# design.net
KiCad netlist of a schematic drawn in EasyEDA Pro
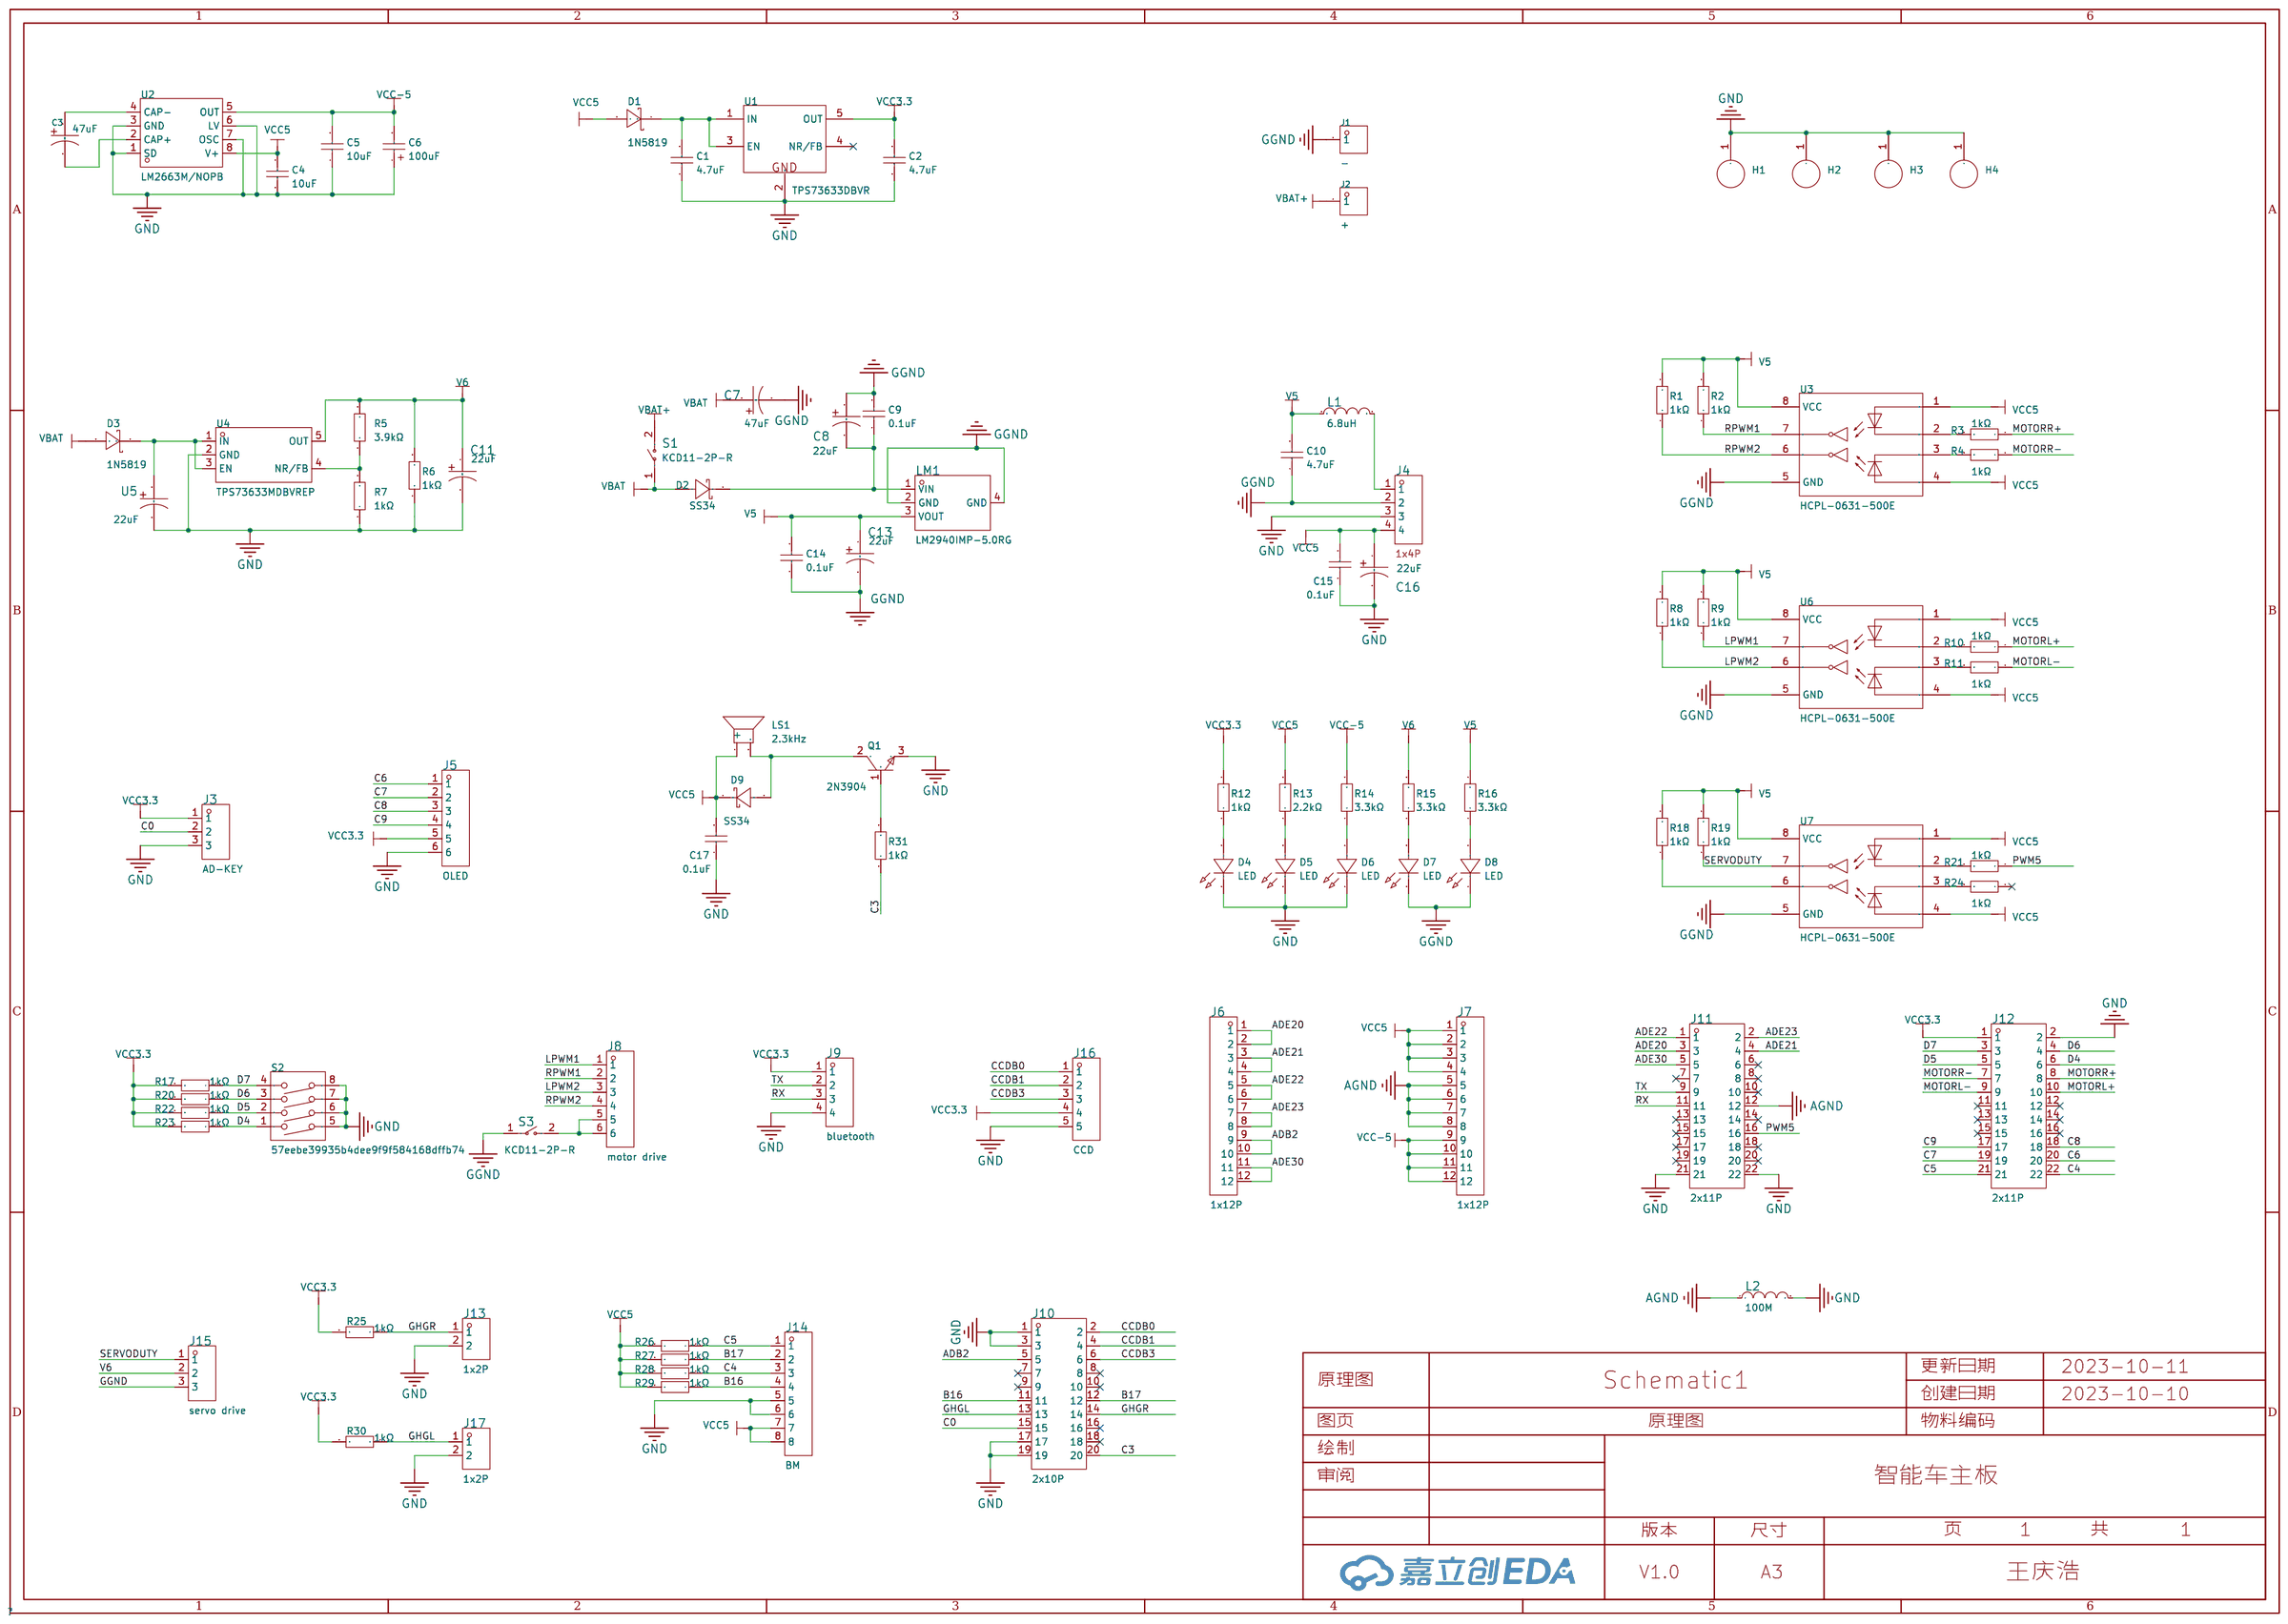
[diagram p0: schematic sheet]

(export (version "E")
  (design (tool "Eeschema 10.0.6"))
  (components
    (comp (ref "C1")
      (value "4.7uF")
      (footprint "easyedapro:C0805")
      (description "容值:10uF;精度:±10%;额定电压:25V;材质(温度系数):X5R;")
      (fields
        (field (name "Manufacturer Part") "CL21A106KAYNNNE")
        (field (name "Manufacturer") "SAMSUNG(三星)")
      )
      (libsource (lib "easyedapro") (part "CL21A106KAYNNNE"))
    )
    (comp (ref "C2")
      (value "4.7uF")
      (footprint "easyedapro:C0805")
      (description "容值:10uF;精度:±10%;额定电压:25V;材质(温度系数):X5R;")
      (fields
        (field (name "Manufacturer Part") "CL21A106KAYNNNE")
        (field (name "Manufacturer") "SAMSUNG(三星)")
      )
      (libsource (lib "easyedapro") (part "CL21A106KAYNNNE"))
    )
    (comp (ref "C3")
      (value "47uF")
      (footprint "easyedapro:CAP-SMD_L6.0-W3.2-R-RD")
      (description "容值:47uF;精度:±20%;额定电压:16V;等效串联电阻:1Ω;")
      (fields
        (field (name "Manufacturer Part") "293D476X0016C2TE3")
        (field (name "Manufacturer") "VISHAY(威世)")
      )
      (libsource (lib "easyedapro") (part "293D476X0016C2TE3"))
    )
    (comp (ref "C4")
      (value "10uF")
      (footprint "easyedapro:C0805")
      (description "容值:10uF;精度:±10%;额定电压:25V;材质(温度系数):X5R;")
      (fields
        (field (name "Manufacturer Part") "CL21A106KAYNNNE")
        (field (name "Manufacturer") "SAMSUNG(三星)")
      )
      (libsource (lib "easyedapro") (part "CL21A106KAYNNNE"))
    )
    (comp (ref "C5")
      (value "10uF")
      (footprint "easyedapro:C0805")
      (description "容值:10uF;精度:±10%;额定电压:25V;材质(温度系数):X5R;")
      (fields
        (field (name "Manufacturer Part") "CL21A106KAYNNNE")
        (field (name "Manufacturer") "SAMSUNG(三星)")
      )
      (libsource (lib "easyedapro") (part "CL21A106KAYNNNE"))
    )
    (comp (ref "C6")
      (value "100uF")
      (footprint "easyedapro:CAP-SMD_L3.2-W1.6-RD-C7171")
      (description "容值:10uF;精度:±10%;额定电压:16V;等效串联电阻:3Ω@100kHz;")
      (fields (field (name "Manufacturer Part") "TAJA106K016RNJ") (field (name "Manufacturer") "Kyocera AVX"))
      (libsource (lib "easyedapro") (part "TAJA106K016RNJ"))
    )
    (comp (ref "C7")
      (value "47uF")
      (footprint "easyedapro:CAP-SMD_L7.3-W4.3-RD")
      (fields
        (field (name "Manufacturer Part") "293D475X9035D2TE3")
        (field (name "Manufacturer") "VISHAY(威世)")
      )
      (libsource (lib "easyedapro") (part "293D475X9035D2TE3"))
    )
    (comp (ref "C8")
      (value "22uF")
      (footprint "easyedapro:CAP-SMD_L6.0-W3.2-R-RD")
      (description "容值:47uF;精度:±20%;额定电压:16V;等效串联电阻:1Ω;")
      (fields
        (field (name "Manufacturer Part") "293D476X0016C2TE3")
        (field (name "Manufacturer") "VISHAY(威世)")
      )
      (libsource (lib "easyedapro") (part "293D476X0016C2TE3"))
    )
    (comp (ref "C9")
      (value "0.1uF")
      (footprint "easyedapro:C0805")
      (description "容值:100nF;精度:±10%;额定电压:50V;材质(温度系数):X7R;")
      (fields
        (field (name "Manufacturer Part") "CC0805KRX7R9BB104")
        (field (name "Manufacturer") "YAGEO(国巨)")
      )
      (libsource (lib "easyedapro") (part "CC0805KRX7R9BB104"))
    )
    (comp (ref "C10")
      (value "4.7uF")
      (footprint "easyedapro:C0805")
      (description "容值:100nF;精度:±10%;额定电压:50V;材质(温度系数):X7R;")
      (fields
        (field (name "Manufacturer Part") "CC0805KRX7R9BB104")
        (field (name "Manufacturer") "YAGEO(国巨)")
      )
      (libsource (lib "easyedapro") (part "CC0805KRX7R9BB104"))
    )
    (comp (ref "C11")
      (value "22uF")
      (footprint "easyedapro:CAP-SMD_L7.3-W4.3-RD")
      (fields
        (field (name "Manufacturer Part") "293D475X9035D2TE3")
        (field (name "Manufacturer") "VISHAY(威世)")
      )
      (libsource (lib "easyedapro") (part "293D475X9035D2TE3"))
    )
    (comp (ref "C13")
      (value "22uF")
      (footprint "easyedapro:CAP-SMD_L7.3-W4.3-RD")
      (fields
        (field (name "Manufacturer Part") "293D475X9035D2TE3")
        (field (name "Manufacturer") "VISHAY(威世)")
      )
      (libsource (lib "easyedapro") (part "293D475X9035D2TE3"))
    )
    (comp (ref "C14")
      (value "0.1uF")
      (footprint "easyedapro:C0805")
      (description "容值:100nF;精度:±10%;额定电压:50V;材质(温度系数):X7R;")
      (fields
        (field (name "Manufacturer Part") "CC0805KRX7R9BB104")
        (field (name "Manufacturer") "YAGEO(国巨)")
      )
      (libsource (lib "easyedapro") (part "CC0805KRX7R9BB104"))
    )
    (comp (ref "C15")
      (value "0.1uF")
      (footprint "easyedapro:C0805")
      (description "容值:100nF;精度:±10%;额定电压:50V;材质(温度系数):X7R;")
      (fields
        (field (name "Manufacturer Part") "CC0805KRX7R9BB104")
        (field (name "Manufacturer") "YAGEO(国巨)")
      )
      (libsource (lib "easyedapro") (part "CC0805KRX7R9BB104"))
    )
    (comp (ref "C16")
      (value "22uF")
      (footprint "easyedapro:CAP-SMD_L7.3-W4.3-RD")
      (fields
        (field (name "Manufacturer Part") "293D475X9035D2TE3")
        (field (name "Manufacturer") "VISHAY(威世)")
      )
      (libsource (lib "easyedapro") (part "293D475X9035D2TE3"))
    )
    (comp (ref "C17")
      (value "0.1uF")
      (footprint "easyedapro:C0805")
      (description "容值:100nF;精度:±10%;额定电压:50V;材质(温度系数):X7R;")
      (fields
        (field (name "Manufacturer Part") "CC0805KRX7R9BB104")
        (field (name "Manufacturer") "YAGEO(国巨)")
      )
      (libsource (lib "easyedapro") (part "CC0805KRX7R9BB104"))
    )
    (comp (ref "D1")
      (value "1N5819")
      (footprint "easyedapro:SMA_L4.4-W2.6-LS5.0-RD")
      (description "直流反向耐压(Vr):40V;平均整流电流(Io):1A;正向压降(Vf):500mV@1A;")
      (fields (field (name "Manufacturer") "KEXIN(科信)"))
      (libsource (lib "easyedapro") (part "1N5819_C437199"))
    )
    (comp (ref "D2")
      (value "SS34")
      (footprint "easyedapro:SMA_L4.3-W2.5-LS5.0-RD")
      (description "二极管配置:独立式;直流反向耐压(Vr):40V;平均整流电流(Io):3A;正向压降(Vf):550mV@3A;")
      (fields (field (name "Manufacturer") "TWGMC(台湾迪嘉)"))
      (libsource (lib "easyedapro") (part "SS34_C727060"))
    )
    (comp (ref "D3")
      (value "1N5819")
      (footprint "easyedapro:SMA_L4.4-W2.6-LS5.0-RD")
      (description "直流反向耐压(Vr):40V;平均整流电流(Io):1A;正向压降(Vf):500mV@1A;")
      (fields (field (name "Manufacturer") "KEXIN(科信)"))
      (libsource (lib "easyedapro") (part "1N5819_C437199"))
    )
    (comp (ref "D4")
      (value "LED")
      (footprint "easyedapro:LED0805-RD_RED")
      (description "发光颜色:红灯;主波长:617nm~621nm;色温:-;功率:55mW;安装方式:正贴;")
      (fields (field (name "Manufacturer Part") "XL-2012SURC") (field (name "Manufacturer") "XINGLIGHT(成兴光)"))
      (libsource (lib "easyedapro") (part "XL-2012SURC"))
    )
    (comp (ref "D5")
      (value "LED")
      (footprint "easyedapro:LED0805-RD_RED")
      (description "发光颜色:红灯;主波长:617nm~621nm;色温:-;功率:55mW;安装方式:正贴;")
      (fields (field (name "Manufacturer Part") "XL-2012SURC") (field (name "Manufacturer") "XINGLIGHT(成兴光)"))
      (libsource (lib "easyedapro") (part "XL-2012SURC"))
    )
    (comp (ref "D6")
      (value "LED")
      (footprint "easyedapro:LED0805-RD_RED")
      (description "发光颜色:红灯;主波长:617nm~621nm;色温:-;功率:55mW;安装方式:正贴;")
      (fields (field (name "Manufacturer Part") "XL-2012SURC") (field (name "Manufacturer") "XINGLIGHT(成兴光)"))
      (libsource (lib "easyedapro") (part "XL-2012SURC"))
    )
    (comp (ref "D7")
      (value "LED")
      (footprint "easyedapro:LED0805-RD_RED")
      (description "发光颜色:红灯;主波长:617nm~621nm;色温:-;功率:55mW;安装方式:正贴;")
      (fields (field (name "Manufacturer Part") "XL-2012SURC") (field (name "Manufacturer") "XINGLIGHT(成兴光)"))
      (libsource (lib "easyedapro") (part "XL-2012SURC"))
    )
    (comp (ref "D8")
      (value "LED")
      (footprint "easyedapro:LED0805-RD_RED")
      (description "发光颜色:红灯;主波长:617nm~621nm;色温:-;功率:55mW;安装方式:正贴;")
      (fields (field (name "Manufacturer Part") "XL-2012SURC") (field (name "Manufacturer") "XINGLIGHT(成兴光)"))
      (libsource (lib "easyedapro") (part "XL-2012SURC"))
    )
    (comp (ref "D9")
      (value "SS34")
      (footprint "easyedapro:SMA_L4.3-W2.5-LS5.0-RD")
      (description "二极管配置:独立式;直流反向耐压(Vr):40V;平均整流电流(Io):3A;正向压降(Vf):550mV@3A;")
      (fields (field (name "Manufacturer") "TWGMC(台湾迪嘉)"))
      (libsource (lib "easyedapro") (part "SS34_C727060"))
    )
    (comp (ref "H1")
      (value "~")
      (footprint "easyedapro:固定孔封装")
      (description "铜柱孔")
      (libsource (lib "easyedapro") (part "固定孔"))
    )
    (comp (ref "H2")
      (value "~")
      (footprint "easyedapro:固定孔封装")
      (description "铜柱孔")
      (libsource (lib "easyedapro") (part "固定孔"))
    )
    (comp (ref "H3")
      (value "~")
      (footprint "easyedapro:固定孔封装")
      (description "铜柱孔")
      (libsource (lib "easyedapro") (part "固定孔"))
    )
    (comp (ref "H4")
      (value "~")
      (footprint "easyedapro:固定孔封装")
      (description "铜柱孔")
      (libsource (lib "easyedapro") (part "固定孔"))
    )
    (comp (ref "J1")
      (value "-")
      (footprint "easyedapro:HDR-SMD_1P-P2.54-V-M_XKB_R1")
      (fields (field (name "Manufacturer") "XKB Connectivity(中国星坤)"))
      (libsource (lib "easyedapro") (part "X6511WVS-01H-C60D48R1"))
    )
    (comp (ref "J2")
      (value "+")
      (footprint "easyedapro:HDR-SMD_1P-P2.54-V-M_XKB_R1")
      (fields (field (name "Manufacturer") "XKB Connectivity(中国星坤)"))
      (libsource (lib "easyedapro") (part "X6511WVS-01H-C60D48R1"))
    )
    (comp (ref "J3")
      (value "AD-KEY")
      (footprint "easyedapro:HDR-TH_3P-P2.54-V-M")
      (fields (field (name "Manufacturer Part") "PZ254V-11-03P") (field (name "Manufacturer") "XFCN(兴飞)"))
      (libsource (lib "easyedapro") (part "PZ254V-11-03P_C2937625"))
    )
    (comp (ref "J4")
      (value "bf6de8a097bd4b3495073099155543ed")
      (footprint "easyedapro:HDR-TH_4P-P2.54-V-M")
      (fields
        (field (name "Manufacturer Part") "PZ254V-11-04P")
        (field (name "Manufacturer") "XFCN(兴飞)")
        (field (name "Pin Structure") "1x4P")
      )
      (libsource (lib "easyedapro") (part "PZ254V-11-04P_C2691448"))
    )
    (comp (ref "J5")
      (value "OLED")
      (footprint "easyedapro:HDR-TH_6P-P2.54-V-M")
      (fields (field (name "Manufacturer Part") "PZ254V-11-06P") (field (name "Manufacturer") "XFCN(兴飞)"))
      (libsource (lib "easyedapro") (part "PZ254V-11-06P"))
    )
    (comp (ref "J6")
      (value "1x12P")
      (footprint "easyedapro:HDR-TH_12P-P2.54-V-M")
      (fields (field (name "Manufacturer Part") "PZ254V-11-12P") (field (name "Manufacturer") "XFCN(兴飞)"))
      (libsource (lib "easyedapro") (part "PZ254V-11-12P"))
    )
    (comp (ref "J7")
      (value "1x12P")
      (footprint "easyedapro:HDR-TH_12P-P2.54-V-M")
      (fields (field (name "Manufacturer Part") "PZ254V-11-12P") (field (name "Manufacturer") "XFCN(兴飞)"))
      (libsource (lib "easyedapro") (part "PZ254V-11-12P"))
    )
    (comp (ref "J8")
      (value "motor drive")
      (footprint "easyedapro:HDR-TH_6P-P2.54-V-M")
      (fields (field (name "Manufacturer Part") "PZ254V-11-06P") (field (name "Manufacturer") "XFCN(兴飞)"))
      (libsource (lib "easyedapro") (part "PZ254V-11-06P"))
    )
    (comp (ref "J9")
      (value "bluetooth")
      (footprint "easyedapro:HDR-TH_4P-P2.54-V-M")
      (fields (field (name "Manufacturer Part") "PZ254V-11-04P") (field (name "Manufacturer") "XFCN(兴飞)"))
      (libsource (lib "easyedapro") (part "PZ254V-11-04P_C2691448"))
    )
    (comp (ref "J10")
      (value "2x10P")
      (footprint "easyedapro:HDR-TH_20P-P2.54-V-M-R2-C10-S2.54")
      (fields (field (name "Manufacturer Part") "PZ254V-12-20P") (field (name "Manufacturer") "XFCN(兴飞)"))
      (libsource (lib "easyedapro") (part "PZ254V-12-20P"))
    )
    (comp (ref "J11")
      (value "2x11P")
      (footprint "easyedapro:HDR-TH_22P-P2.54-V-M-R2-C11-S2.54")
      (fields
        (field (name "Manufacturer Part") "PZ254-2-11-Z-8.5")
        (field (name "Manufacturer") "HCTL(华灿天禄)")
      )
      (libsource (lib "easyedapro") (part "PZ254-2-11-Z-8.5"))
    )
    (comp (ref "J12")
      (value "2x11P")
      (footprint "easyedapro:HDR-TH_22P-P2.54-V-M-R2-C11-S2.54")
      (fields
        (field (name "Manufacturer Part") "PZ254-2-11-Z-8.5")
        (field (name "Manufacturer") "HCTL(华灿天禄)")
      )
      (libsource (lib "easyedapro") (part "PZ254-2-11-Z-8.5"))
    )
    (comp (ref "J13")
      (value "1x2P")
      (footprint "easyedapro:HDR-TH_2P-P2.54-V-M")
      (fields (field (name "Manufacturer Part") "PZ254V-11-02P") (field (name "Manufacturer") "XFCN(兴飞)"))
      (libsource (lib "easyedapro") (part "PZ254V-11-02P"))
    )
    (comp (ref "J14")
      (value "BM")
      (footprint "easyedapro:HDR-TH_8P-P2.54-V-M")
      (fields (field (name "Manufacturer Part") "PZ254V-11-08P") (field (name "Manufacturer") "XFCN(兴飞)"))
      (libsource (lib "easyedapro") (part "PZ254V-11-08P"))
    )
    (comp (ref "J15")
      (value "servo drive")
      (footprint "easyedapro:HDR-TH_3P-P2.54-V-M")
      (fields (field (name "Manufacturer Part") "PZ254V-11-03P") (field (name "Manufacturer") "XFCN(兴飞)"))
      (libsource (lib "easyedapro") (part "PZ254V-11-03P_C2937625"))
    )
    (comp (ref "J16")
      (value "CCD")
      (footprint "easyedapro:HDR-TH_5P-P2.00-V-M")
      (fields (field (name "Manufacturer Part") "PZ200V-11-05P") (field (name "Manufacturer") "XFCN(兴飞)"))
      (libsource (lib "easyedapro") (part "PZ200V-11-05P"))
    )
    (comp (ref "J17")
      (value "1x2P")
      (footprint "easyedapro:HDR-TH_2P-P2.54-V-M")
      (fields (field (name "Manufacturer Part") "PZ254V-11-02P") (field (name "Manufacturer") "XFCN(兴飞)"))
      (libsource (lib "easyedapro") (part "PZ254V-11-02P"))
    )
    (comp (ref "L1")
      (value "6.8uH")
      (footprint "easyedapro:L0603")
      (description "电感值:10uH;精度:±10%;额定电流:3mA;饱和电流(Isat):-;直流电阻(DCR):1.85Ω;")
      (fields
        (field (name "Manufacturer Part") "SDFL1608S100KTF")
        (field (name "Manufacturer") "Sunlord(顺络)")
      )
      (libsource (lib "easyedapro") (part "SDFL1608S100KTF"))
    )
    (comp (ref "L2")
      (value "100M")
      (footprint "easyedapro:L0603")
      (description "电感值:10uH;精度:±10%;额定电流:3mA;饱和电流(Isat):-;直流电阻(DCR):1.85Ω;")
      (fields
        (field (name "Manufacturer Part") "SDFL1608S100KTF")
        (field (name "Manufacturer") "Sunlord(顺络)")
      )
      (libsource (lib "easyedapro") (part "SDFL1608S100KTF"))
    )
    (comp (ref "LM1")
      (value "LM2940IMP-5.0RG")
      (footprint "easyedapro:SOT-223-4_L6.5-W3.5-P2.30-LS7.0-BR")
      (fields (field (name "Manufacturer") "HGC(深圳汉芯)"))
      (libsource (lib "easyedapro") (part "LM2940IMP-5.0RG"))
    )
    (comp (ref "LS1")
      (value "2.3kHz")
      (footprint "easyedapro:BUZ-TH_BD12.0-P7.60-D0.6-FD")
      (description "驱动方式:有源(内含驱动线路);构造类型:电磁式;额定电压:5V;频率:2.3kHz;声压(SPL):85dB@5V,10cm;")
      (fields (field (name "Manufacturer Part") "TMB12A05") (field (name "Manufacturer") "华能"))
      (libsource (lib "easyedapro") (part "TMB12A05"))
    )
    (comp (ref "Q1")
      (value "2N3904")
      (footprint "easyedapro:TO-92-3_L4.6-W3.6-P1.30-L_2N3904")
      (fields (field (name "Manufacturer") "JSMSEMI(杰盛微)"))
      (libsource (lib "easyedapro") (part "2N3904_C2874602"))
    )
    (comp (ref "R1")
      (value "1kΩ")
      (footprint "easyedapro:R0805")
      (description "电阻类型:厚膜电阻;阻值:3.9kΩ;精度:±1%;功率:125mW;")
      (fields
        (field (name "Manufacturer Part") "0805W8F3901T5E")
        (field (name "Manufacturer") "UNI-ROYAL(厚声)")
      )
      (libsource (lib "easyedapro") (part "0805W8F3901T5E"))
    )
    (comp (ref "R2")
      (value "1kΩ")
      (footprint "easyedapro:R0805")
      (description "电阻类型:厚膜电阻;阻值:3.9kΩ;精度:±1%;功率:125mW;")
      (fields
        (field (name "Manufacturer Part") "0805W8F3901T5E")
        (field (name "Manufacturer") "UNI-ROYAL(厚声)")
      )
      (libsource (lib "easyedapro") (part "0805W8F3901T5E"))
    )
    (comp (ref "R3")
      (value "1kΩ")
      (footprint "easyedapro:R0805")
      (description "电阻类型:厚膜电阻;阻值:3.9kΩ;精度:±1%;功率:125mW;")
      (fields
        (field (name "Manufacturer Part") "0805W8F3901T5E")
        (field (name "Manufacturer") "UNI-ROYAL(厚声)")
      )
      (libsource (lib "easyedapro") (part "0805W8F3901T5E"))
    )
    (comp (ref "R4")
      (value "1kΩ")
      (footprint "easyedapro:R0805")
      (description "电阻类型:厚膜电阻;阻值:3.9kΩ;精度:±1%;功率:125mW;")
      (fields
        (field (name "Manufacturer Part") "0805W8F3901T5E")
        (field (name "Manufacturer") "UNI-ROYAL(厚声)")
      )
      (libsource (lib "easyedapro") (part "0805W8F3901T5E"))
    )
    (comp (ref "R5")
      (value "3.9kΩ")
      (footprint "easyedapro:R0805")
      (description "电阻类型:厚膜电阻;阻值:3.9kΩ;精度:±1%;功率:125mW;")
      (fields
        (field (name "Manufacturer Part") "0805W8F3901T5E")
        (field (name "Manufacturer") "UNI-ROYAL(厚声)")
      )
      (libsource (lib "easyedapro") (part "0805W8F3901T5E"))
    )
    (comp (ref "R6")
      (value "1kΩ")
      (footprint "easyedapro:R0805")
      (description "电阻类型:厚膜电阻;阻值:3.9kΩ;精度:±1%;功率:125mW;")
      (fields
        (field (name "Manufacturer Part") "0805W8F3901T5E")
        (field (name "Manufacturer") "UNI-ROYAL(厚声)")
      )
      (libsource (lib "easyedapro") (part "0805W8F3901T5E"))
    )
    (comp (ref "R7")
      (value "1kΩ")
      (footprint "easyedapro:R0805")
      (description "电阻类型:厚膜电阻;阻值:3.9kΩ;精度:±1%;功率:125mW;")
      (fields
        (field (name "Manufacturer Part") "0805W8F3901T5E")
        (field (name "Manufacturer") "UNI-ROYAL(厚声)")
      )
      (libsource (lib "easyedapro") (part "0805W8F3901T5E"))
    )
    (comp (ref "R8")
      (value "1kΩ")
      (footprint "easyedapro:R0805")
      (description "电阻类型:厚膜电阻;阻值:3.9kΩ;精度:±1%;功率:125mW;")
      (fields
        (field (name "Manufacturer Part") "0805W8F3901T5E")
        (field (name "Manufacturer") "UNI-ROYAL(厚声)")
      )
      (libsource (lib "easyedapro") (part "0805W8F3901T5E"))
    )
    (comp (ref "R9")
      (value "1kΩ")
      (footprint "easyedapro:R0805")
      (description "电阻类型:厚膜电阻;阻值:3.9kΩ;精度:±1%;功率:125mW;")
      (fields
        (field (name "Manufacturer Part") "0805W8F3901T5E")
        (field (name "Manufacturer") "UNI-ROYAL(厚声)")
      )
      (libsource (lib "easyedapro") (part "0805W8F3901T5E"))
    )
    (comp (ref "R10")
      (value "1kΩ")
      (footprint "easyedapro:R0805")
      (description "电阻类型:厚膜电阻;阻值:3.9kΩ;精度:±1%;功率:125mW;")
      (fields
        (field (name "Manufacturer Part") "0805W8F3901T5E")
        (field (name "Manufacturer") "UNI-ROYAL(厚声)")
      )
      (libsource (lib "easyedapro") (part "0805W8F3901T5E"))
    )
    (comp (ref "R11")
      (value "1kΩ")
      (footprint "easyedapro:R0805")
      (description "电阻类型:厚膜电阻;阻值:3.9kΩ;精度:±1%;功率:125mW;")
      (fields
        (field (name "Manufacturer Part") "0805W8F3901T5E")
        (field (name "Manufacturer") "UNI-ROYAL(厚声)")
      )
      (libsource (lib "easyedapro") (part "0805W8F3901T5E"))
    )
    (comp (ref "R12")
      (value "1kΩ")
      (footprint "easyedapro:R0805")
      (description "电阻类型:厚膜电阻;阻值:3.9kΩ;精度:±1%;功率:125mW;")
      (fields
        (field (name "Manufacturer Part") "0805W8F3901T5E")
        (field (name "Manufacturer") "UNI-ROYAL(厚声)")
      )
      (libsource (lib "easyedapro") (part "0805W8F3901T5E"))
    )
    (comp (ref "R13")
      (value "2.2kΩ")
      (footprint "easyedapro:R0805")
      (description "电阻类型:厚膜电阻;阻值:3.9kΩ;精度:±1%;功率:125mW;")
      (fields
        (field (name "Manufacturer Part") "0805W8F3901T5E")
        (field (name "Manufacturer") "UNI-ROYAL(厚声)")
      )
      (libsource (lib "easyedapro") (part "0805W8F3901T5E"))
    )
    (comp (ref "R14")
      (value "3.3kΩ")
      (footprint "easyedapro:R0805")
      (description "电阻类型:厚膜电阻;阻值:3.9kΩ;精度:±1%;功率:125mW;")
      (fields
        (field (name "Manufacturer Part") "0805W8F3901T5E")
        (field (name "Manufacturer") "UNI-ROYAL(厚声)")
      )
      (libsource (lib "easyedapro") (part "0805W8F3901T5E"))
    )
    (comp (ref "R15")
      (value "3.3kΩ")
      (footprint "easyedapro:R0805")
      (description "电阻类型:厚膜电阻;阻值:3.9kΩ;精度:±1%;功率:125mW;")
      (fields
        (field (name "Manufacturer Part") "0805W8F3901T5E")
        (field (name "Manufacturer") "UNI-ROYAL(厚声)")
      )
      (libsource (lib "easyedapro") (part "0805W8F3901T5E"))
    )
    (comp (ref "R16")
      (value "3.3kΩ")
      (footprint "easyedapro:R0805")
      (description "电阻类型:厚膜电阻;阻值:3.9kΩ;精度:±1%;功率:125mW;")
      (fields
        (field (name "Manufacturer Part") "0805W8F3901T5E")
        (field (name "Manufacturer") "UNI-ROYAL(厚声)")
      )
      (libsource (lib "easyedapro") (part "0805W8F3901T5E"))
    )
    (comp (ref "R17")
      (value "1kΩ")
      (footprint "easyedapro:R0805")
      (description "电阻类型:厚膜电阻;阻值:3.9kΩ;精度:±1%;功率:125mW;")
      (fields
        (field (name "Manufacturer Part") "0805W8F3901T5E")
        (field (name "Manufacturer") "UNI-ROYAL(厚声)")
      )
      (libsource (lib "easyedapro") (part "0805W8F3901T5E"))
    )
    (comp (ref "R18")
      (value "1kΩ")
      (footprint "easyedapro:R0805")
      (description "电阻类型:厚膜电阻;阻值:3.9kΩ;精度:±1%;功率:125mW;")
      (fields
        (field (name "Manufacturer Part") "0805W8F3901T5E")
        (field (name "Manufacturer") "UNI-ROYAL(厚声)")
      )
      (libsource (lib "easyedapro") (part "0805W8F3901T5E"))
    )
    (comp (ref "R19")
      (value "1kΩ")
      (footprint "easyedapro:R0805")
      (description "电阻类型:厚膜电阻;阻值:3.9kΩ;精度:±1%;功率:125mW;")
      (fields
        (field (name "Manufacturer Part") "0805W8F3901T5E")
        (field (name "Manufacturer") "UNI-ROYAL(厚声)")
      )
      (libsource (lib "easyedapro") (part "0805W8F3901T5E"))
    )
    (comp (ref "R20")
      (value "1kΩ")
      (footprint "easyedapro:R0805")
      (description "电阻类型:厚膜电阻;阻值:3.9kΩ;精度:±1%;功率:125mW;")
      (fields
        (field (name "Manufacturer Part") "0805W8F3901T5E")
        (field (name "Manufacturer") "UNI-ROYAL(厚声)")
      )
      (libsource (lib "easyedapro") (part "0805W8F3901T5E"))
    )
    (comp (ref "R21")
      (value "1kΩ")
      (footprint "easyedapro:R0805")
      (description "电阻类型:厚膜电阻;阻值:3.9kΩ;精度:±1%;功率:125mW;")
      (fields
        (field (name "Manufacturer Part") "0805W8F3901T5E")
        (field (name "Manufacturer") "UNI-ROYAL(厚声)")
      )
      (libsource (lib "easyedapro") (part "0805W8F3901T5E"))
    )
    (comp (ref "R22")
      (value "1kΩ")
      (footprint "easyedapro:R0805")
      (description "电阻类型:厚膜电阻;阻值:3.9kΩ;精度:±1%;功率:125mW;")
      (fields
        (field (name "Manufacturer Part") "0805W8F3901T5E")
        (field (name "Manufacturer") "UNI-ROYAL(厚声)")
      )
      (libsource (lib "easyedapro") (part "0805W8F3901T5E"))
    )
    (comp (ref "R23")
      (value "1kΩ")
      (footprint "easyedapro:R0805")
      (description "电阻类型:厚膜电阻;阻值:3.9kΩ;精度:±1%;功率:125mW;")
      (fields
        (field (name "Manufacturer Part") "0805W8F3901T5E")
        (field (name "Manufacturer") "UNI-ROYAL(厚声)")
      )
      (libsource (lib "easyedapro") (part "0805W8F3901T5E"))
    )
    (comp (ref "R24")
      (value "1kΩ")
      (footprint "easyedapro:R0805")
      (description "电阻类型:厚膜电阻;阻值:3.9kΩ;精度:±1%;功率:125mW;")
      (fields
        (field (name "Manufacturer Part") "0805W8F3901T5E")
        (field (name "Manufacturer") "UNI-ROYAL(厚声)")
      )
      (libsource (lib "easyedapro") (part "0805W8F3901T5E"))
    )
    (comp (ref "R25")
      (value "1kΩ")
      (footprint "easyedapro:R0805")
      (description "电阻类型:厚膜电阻;阻值:3.9kΩ;精度:±1%;功率:125mW;")
      (fields
        (field (name "Manufacturer Part") "0805W8F3901T5E")
        (field (name "Manufacturer") "UNI-ROYAL(厚声)")
      )
      (libsource (lib "easyedapro") (part "0805W8F3901T5E"))
    )
    (comp (ref "R26")
      (value "1kΩ")
      (footprint "easyedapro:R0805")
      (description "电阻类型:厚膜电阻;阻值:3.9kΩ;精度:±1%;功率:125mW;")
      (fields
        (field (name "Manufacturer Part") "0805W8F3901T5E")
        (field (name "Manufacturer") "UNI-ROYAL(厚声)")
      )
      (libsource (lib "easyedapro") (part "0805W8F3901T5E"))
    )
    (comp (ref "R27")
      (value "1kΩ")
      (footprint "easyedapro:R0805")
      (description "电阻类型:厚膜电阻;阻值:3.9kΩ;精度:±1%;功率:125mW;")
      (fields
        (field (name "Manufacturer Part") "0805W8F3901T5E")
        (field (name "Manufacturer") "UNI-ROYAL(厚声)")
      )
      (libsource (lib "easyedapro") (part "0805W8F3901T5E"))
    )
    (comp (ref "R28")
      (value "1kΩ")
      (footprint "easyedapro:R0805")
      (description "电阻类型:厚膜电阻;阻值:3.9kΩ;精度:±1%;功率:125mW;")
      (fields
        (field (name "Manufacturer Part") "0805W8F3901T5E")
        (field (name "Manufacturer") "UNI-ROYAL(厚声)")
      )
      (libsource (lib "easyedapro") (part "0805W8F3901T5E"))
    )
    (comp (ref "R29")
      (value "1kΩ")
      (footprint "easyedapro:R0805")
      (description "电阻类型:厚膜电阻;阻值:3.9kΩ;精度:±1%;功率:125mW;")
      (fields
        (field (name "Manufacturer Part") "0805W8F3901T5E")
        (field (name "Manufacturer") "UNI-ROYAL(厚声)")
      )
      (libsource (lib "easyedapro") (part "0805W8F3901T5E"))
    )
    (comp (ref "R30")
      (value "1kΩ")
      (footprint "easyedapro:R0805")
      (description "电阻类型:厚膜电阻;阻值:3.9kΩ;精度:±1%;功率:125mW;")
      (fields
        (field (name "Manufacturer Part") "0805W8F3901T5E")
        (field (name "Manufacturer") "UNI-ROYAL(厚声)")
      )
      (libsource (lib "easyedapro") (part "0805W8F3901T5E"))
    )
    (comp (ref "R31")
      (value "1kΩ")
      (footprint "easyedapro:R0805")
      (description "电阻类型:厚膜电阻;阻值:3.9kΩ;精度:±1%;功率:125mW;")
      (fields
        (field (name "Manufacturer Part") "0805W8F3901T5E")
        (field (name "Manufacturer") "UNI-ROYAL(厚声)")
      )
      (libsource (lib "easyedapro") (part "0805W8F3901T5E"))
    )
    (comp (ref "S1")
      (value "KCD11-2P-R")
      (footprint "easyedapro:SW-TH_2P-L15.0-W10.5-P5.00_KCD11-2P-R")
      (description "额定电流:3A;额定电压(AC):250V;额定电压(DC):-;电路结构:单刀单掷;机械寿命:1万次;带灯:无;引脚样式:焊片;")
      (fields (field (name "Manufacturer") "SHOU HAN(首韩)"))
      (libsource (lib "easyedapro") (part "KCD11-2P-R"))
    )
    (comp (ref "S2")
      (value "57eebe39935b4dee9f9f584168dffb74")
      (footprint "easyedapro:SW-TH_DSWB04LHGET")
      (description "类型:平拨,凸起式;电路结构:单刀单掷;开关位数:4;使用寿命:-;颜色:红色;")
      (fields (field (name "Manufacturer Part") "DSWB04LHGET") (field (name "Manufacturer") "YE"))
      (libsource (lib "easyedapro") (part "DSWB04LHGET"))
    )
    (comp (ref "S3")
      (value "KCD11-2P-R")
      (footprint "easyedapro:SW-TH_2P-L15.0-W10.5-P5.00_KCD11-2P-R")
      (description "额定电流:3A;额定电压(AC):250V;额定电压(DC):-;电路结构:单刀单掷;机械寿命:1万次;带灯:无;引脚样式:焊片;")
      (fields (field (name "Manufacturer") "SHOU HAN(首韩)"))
      (libsource (lib "easyedapro") (part "KCD11-2P-R"))
    )
    (comp (ref "U1")
      (value "TPS73633DBVR")
      (footprint "easyedapro:SOT-23-5_L3.0-W1.7-P0.95-LS2.8-BR")
      (description "输出类型:固定;输出极性:正;最大输入电压:5.5V;输出电压:3.3V;输出电流:400mA;电源纹波抑制比(PSRR):58dB;")
      (fields (field (name "Manufacturer") "TI(德州仪器)"))
      (libsource (lib "easyedapro") (part "TPS73633DBVR"))
    )
    (comp (ref "U2")
      (value "LM2663M/NOPB")
      (footprint "easyedapro:SOIC-8_L4.9-W3.9-P1.27-LS6.0-BL")
      (description "LM2663 具有低电流关断模式的 200mA 开关电容器电压转换器")
      (fields (field (name "Manufacturer") "TI(德州仪器)"))
      (libsource (lib "easyedapro") (part "LM2663M/NOPB"))
    )
    (comp (ref "U3")
      (value "HCPL-0631-500E")
      (footprint "easyedapro:SOIC-8_L4.9-W3.9-P1.27-LS6.0-BL")
      (fields (field (name "Manufacturer") "AVAGO(安华高)"))
      (libsource (lib "easyedapro") (part "HCPL-0631-500E"))
    )
    (comp (ref "U4")
      (value "TPS73633MDBVREP")
      (footprint "easyedapro:SOT-23-5_L2.9-W1.6-P0.95-LS2.8-BR")
      (fields (field (name "Manufacturer") "TI(德州仪器)"))
      (libsource (lib "easyedapro") (part "TPS73633MDBVREP"))
    )
    (comp (ref "U5")
      (value "22uF")
      (footprint "easyedapro:CAP-SMD_L7.3-W4.3-RD")
      (fields (field (name "Manufacturer") "VISHAY(威世)"))
      (libsource (lib "easyedapro") (part "293D475X9035D2TE3"))
    )
    (comp (ref "U6")
      (value "HCPL-0631-500E")
      (footprint "easyedapro:SOIC-8_L4.9-W3.9-P1.27-LS6.0-BL")
      (fields (field (name "Manufacturer") "AVAGO(安华高)"))
      (libsource (lib "easyedapro") (part "HCPL-0631-500E"))
    )
    (comp (ref "U7")
      (value "HCPL-0631-500E")
      (footprint "easyedapro:SOIC-8_L4.9-W3.9-P1.27-LS6.0-BL")
      (fields (field (name "Manufacturer") "AVAGO(安华高)"))
      (libsource (lib "easyedapro") (part "HCPL-0631-500E"))
    )
  )
  (nets
    (net (code "1") (name "/ADB2") (class "Default")
      (node (ref "J10") (pin "5") (pinfunction "5_5") (pintype "input"))
      (node (ref "J6") (pin "10") (pinfunction "10_10") (pintype "input"))
      (node (ref "J6") (pin "9") (pinfunction "9_9") (pintype "input"))
    )
    (net (code "2") (name "/ADE20") (class "Default")
      (node (ref "J11") (pin "3") (pinfunction "3_3") (pintype "input"))
      (node (ref "J6") (pin "1") (pinfunction "1_1") (pintype "input"))
      (node (ref "J6") (pin "2") (pinfunction "2_2") (pintype "input"))
    )
    (net (code "3") (name "/ADE21") (class "Default")
      (node (ref "J11") (pin "4") (pinfunction "4_4") (pintype "input"))
      (node (ref "J6") (pin "3") (pinfunction "3_3") (pintype "input"))
      (node (ref "J6") (pin "4") (pinfunction "4_4") (pintype "input"))
    )
    (net (code "4") (name "/ADE22") (class "Default")
      (node (ref "J11") (pin "1") (pinfunction "1_1") (pintype "input"))
      (node (ref "J6") (pin "5") (pinfunction "5_5") (pintype "input"))
      (node (ref "J6") (pin "6") (pinfunction "6_6") (pintype "input"))
    )
    (net (code "5") (name "/ADE23") (class "Default")
      (node (ref "J11") (pin "2") (pinfunction "2_2") (pintype "input"))
      (node (ref "J6") (pin "7") (pinfunction "7_7") (pintype "input"))
      (node (ref "J6") (pin "8") (pinfunction "8_8") (pintype "input"))
    )
    (net (code "6") (name "/ADE30") (class "Default")
      (node (ref "J11") (pin "5") (pinfunction "5_5") (pintype "input"))
      (node (ref "J6") (pin "11") (pinfunction "11_11") (pintype "input"))
      (node (ref "J6") (pin "12") (pinfunction "12_12") (pintype "input"))
    )
    (net (code "7") (name "/B16") (class "Default")
      (node (ref "J10") (pin "11") (pinfunction "11_11") (pintype "input"))
      (node (ref "J14") (pin "4") (pinfunction "4_4") (pintype "input"))
      (node (ref "R29") (pin "1") (pinfunction "1_1") (pintype "input"))
    )
    (net (code "8") (name "/B17") (class "Default")
      (node (ref "J10") (pin "12") (pinfunction "12_12") (pintype "input"))
      (node (ref "J14") (pin "2") (pinfunction "2_2") (pintype "input"))
      (node (ref "R27") (pin "1") (pinfunction "1_1") (pintype "input"))
    )
    (net (code "9") (name "/C0") (class "Default")
      (node (ref "J10") (pin "15") (pinfunction "15_15") (pintype "input"))
      (node (ref "J3") (pin "2") (pinfunction "2_2") (pintype "input"))
    )
    (net (code "10") (name "/C3") (class "Default")
      (node (ref "J10") (pin "20") (pinfunction "20_20") (pintype "input"))
      (node (ref "R31") (pin "1") (pinfunction "1_1") (pintype "input"))
    )
    (net (code "11") (name "/C4") (class "Default")
      (node (ref "J12") (pin "22") (pinfunction "22_22") (pintype "input"))
      (node (ref "J14") (pin "3") (pinfunction "3_3") (pintype "input"))
      (node (ref "R28") (pin "1") (pinfunction "1_1") (pintype "input"))
    )
    (net (code "12") (name "/C5") (class "Default")
      (node (ref "J12") (pin "21") (pinfunction "21_21") (pintype "input"))
      (node (ref "J14") (pin "1") (pinfunction "1_1") (pintype "input"))
      (node (ref "R26") (pin "1") (pinfunction "1_1") (pintype "input"))
    )
    (net (code "13") (name "/C6") (class "Default")
      (node (ref "J12") (pin "20") (pinfunction "20_20") (pintype "input"))
      (node (ref "J5") (pin "1") (pinfunction "1_1") (pintype "input"))
    )
    (net (code "14") (name "/C7") (class "Default")
      (node (ref "J12") (pin "19") (pinfunction "19_19") (pintype "input"))
      (node (ref "J5") (pin "2") (pinfunction "2_2") (pintype "input"))
    )
    (net (code "15") (name "/C8") (class "Default")
      (node (ref "J12") (pin "18") (pinfunction "18_18") (pintype "input"))
      (node (ref "J5") (pin "3") (pinfunction "3_3") (pintype "input"))
    )
    (net (code "16") (name "/C9") (class "Default")
      (node (ref "J12") (pin "17") (pinfunction "17_17") (pintype "input"))
      (node (ref "J5") (pin "4") (pinfunction "4_4") (pintype "input"))
    )
    (net (code "17") (name "/CCDB0") (class "Default")
      (node (ref "J10") (pin "2") (pinfunction "2_2") (pintype "input"))
      (node (ref "J16") (pin "1") (pinfunction "1_1") (pintype "input"))
    )
    (net (code "18") (name "/CCDB1") (class "Default")
      (node (ref "J10") (pin "4") (pinfunction "4_4") (pintype "input"))
      (node (ref "J16") (pin "2") (pinfunction "2_2") (pintype "input"))
    )
    (net (code "19") (name "/CCDB3") (class "Default")
      (node (ref "J10") (pin "6") (pinfunction "6_6") (pintype "input"))
      (node (ref "J16") (pin "3") (pinfunction "3_3") (pintype "input"))
    )
    (net (code "20") (name "/D4") (class "Default")
      (node (ref "J12") (pin "6") (pinfunction "6_6") (pintype "input"))
      (node (ref "R23") (pin "1") (pinfunction "1_1") (pintype "input"))
      (node (ref "S2") (pin "1") (pinfunction "1_1") (pintype "input"))
    )
    (net (code "21") (name "/D5") (class "Default")
      (node (ref "J12") (pin "5") (pinfunction "5_5") (pintype "input"))
      (node (ref "R22") (pin "1") (pinfunction "1_1") (pintype "input"))
      (node (ref "S2") (pin "2") (pinfunction "2_2") (pintype "input"))
    )
    (net (code "22") (name "/D6") (class "Default")
      (node (ref "J12") (pin "4") (pinfunction "4_4") (pintype "input"))
      (node (ref "R20") (pin "1") (pinfunction "1_1") (pintype "input"))
      (node (ref "S2") (pin "3") (pinfunction "3_3") (pintype "input"))
    )
    (net (code "23") (name "/D7") (class "Default")
      (node (ref "J12") (pin "3") (pinfunction "3_3") (pintype "input"))
      (node (ref "R17") (pin "1") (pinfunction "1_1") (pintype "input"))
      (node (ref "S2") (pin "4") (pinfunction "4_4") (pintype "input"))
    )
    (net (code "24") (name "/GHGL") (class "Default")
      (node (ref "J10") (pin "13") (pinfunction "13_13") (pintype "input"))
      (node (ref "J17") (pin "1") (pinfunction "1_1") (pintype "input"))
      (node (ref "R30") (pin "1") (pinfunction "1_1") (pintype "input"))
    )
    (net (code "25") (name "/GHGR") (class "Default")
      (node (ref "J10") (pin "14") (pinfunction "14_14") (pintype "input"))
      (node (ref "J13") (pin "1") (pinfunction "1_1") (pintype "input"))
      (node (ref "R25") (pin "1") (pinfunction "1_1") (pintype "input"))
    )
    (net (code "26") (name "/LPWM1") (class "Default")
      (node (ref "J8") (pin "1") (pinfunction "1_1") (pintype "input"))
      (node (ref "R9") (pin "1") (pinfunction "1_1") (pintype "input"))
      (node (ref "U6") (pin "7") (pinfunction "VO1_7") (pintype "input"))
    )
    (net (code "27") (name "/LPWM2") (class "Default")
      (node (ref "J8") (pin "3") (pinfunction "3_3") (pintype "input"))
      (node (ref "R8") (pin "1") (pinfunction "1_1") (pintype "input"))
      (node (ref "U6") (pin "6") (pinfunction "VO2_6") (pintype "input"))
    )
    (net (code "28") (name "/MOTORL+") (class "Default")
      (node (ref "J12") (pin "10") (pinfunction "10_10") (pintype "input"))
      (node (ref "R10") (pin "1") (pinfunction "1_1") (pintype "input"))
    )
    (net (code "29") (name "/MOTORL-") (class "Default")
      (node (ref "J12") (pin "9") (pinfunction "9_9") (pintype "input"))
      (node (ref "R11") (pin "1") (pinfunction "1_1") (pintype "input"))
    )
    (net (code "30") (name "/MOTORR+") (class "Default")
      (node (ref "J12") (pin "8") (pinfunction "8_8") (pintype "input"))
      (node (ref "R3") (pin "1") (pinfunction "1_1") (pintype "input"))
    )
    (net (code "31") (name "/MOTORR-") (class "Default")
      (node (ref "J12") (pin "7") (pinfunction "7_7") (pintype "input"))
      (node (ref "R4") (pin "1") (pinfunction "1_1") (pintype "input"))
    )
    (net (code "32") (name "/PWM5") (class "Default")
      (node (ref "J11") (pin "16") (pinfunction "16_16") (pintype "input"))
      (node (ref "R21") (pin "1") (pinfunction "1_1") (pintype "input"))
    )
    (net (code "33") (name "/RPWM1") (class "Default")
      (node (ref "J8") (pin "2") (pinfunction "2_2") (pintype "input"))
      (node (ref "R2") (pin "1") (pinfunction "1_1") (pintype "input"))
      (node (ref "U3") (pin "7") (pinfunction "VO1_7") (pintype "input"))
    )
    (net (code "34") (name "/RPWM2") (class "Default")
      (node (ref "J8") (pin "4") (pinfunction "4_4") (pintype "input"))
      (node (ref "R1") (pin "1") (pinfunction "1_1") (pintype "input"))
      (node (ref "U3") (pin "6") (pinfunction "VO2_6") (pintype "input"))
    )
    (net (code "35") (name "/RX") (class "Default")
      (node (ref "J11") (pin "11") (pinfunction "11_11") (pintype "input"))
      (node (ref "J9") (pin "3") (pinfunction "3_3") (pintype "input"))
    )
    (net (code "36") (name "/SERVODUTY") (class "Default")
      (node (ref "J15") (pin "1") (pinfunction "1_1") (pintype "input"))
      (node (ref "R19") (pin "1") (pinfunction "1_1") (pintype "input"))
      (node (ref "U7") (pin "7") (pinfunction "VO1_7") (pintype "input"))
    )
    (net (code "37") (name "/TX") (class "Default")
      (node (ref "J11") (pin "9") (pinfunction "9_9") (pintype "input"))
      (node (ref "J9") (pin "2") (pinfunction "2_2") (pintype "input"))
    )
    (net (code "38") (name "AGND") (class "Default")
      (node (ref "J11") (pin "12") (pinfunction "12_12") (pintype "input"))
      (node (ref "J7") (pin "5") (pinfunction "5_5") (pintype "input"))
      (node (ref "J7") (pin "6") (pinfunction "6_6") (pintype "input"))
      (node (ref "J7") (pin "7") (pinfunction "7_7") (pintype "input"))
      (node (ref "J7") (pin "8") (pinfunction "8_8") (pintype "input"))
      (node (ref "L2") (pin "1") (pinfunction "1_1") (pintype "input"))
    )
    (net (code "39") (name "GGND") (class "Default")
      (node (ref "C10") (pin "1") (pinfunction "1_1") (pintype "input"))
      (node (ref "C13") (pin "2") (pinfunction "2_2") (pintype "input"))
      (node (ref "C14") (pin "1") (pinfunction "1_1") (pintype "input"))
      (node (ref "C7") (pin "2") (pinfunction "2_2") (pintype "input"))
      (node (ref "C8") (pin "1") (pinfunction "1_1") (pintype "input"))
      (node (ref "C9") (pin "2") (pinfunction "2_2") (pintype "input"))
      (node (ref "D7") (pin "1") (pinfunction "K_1") (pintype "input"))
      (node (ref "D8") (pin "1") (pinfunction "K_1") (pintype "input"))
      (node (ref "J1") (pin "1") (pinfunction "1_1") (pintype "input"))
      (node (ref "J15") (pin "3") (pinfunction "3_3") (pintype "input"))
      (node (ref "J4") (pin "2") (pinfunction "2_2") (pintype "input"))
      (node (ref "LM1") (pin "2") (pinfunction "GND_2") (pintype "input"))
      (node (ref "LM1") (pin "4") (pinfunction "GND_4") (pintype "input"))
      (node (ref "S3") (pin "1") (pinfunction "1_1") (pintype "input"))
      (node (ref "U3") (pin "5") (pinfunction "GND_5") (pintype "input"))
      (node (ref "U6") (pin "5") (pinfunction "GND_5") (pintype "input"))
      (node (ref "U7") (pin "5") (pinfunction "GND_5") (pintype "input"))
    )
    (net (code "40") (name "GND") (class "Default")
      (node (ref "C1") (pin "1") (pinfunction "1_1") (pintype "input"))
      (node (ref "C11") (pin "2") (pinfunction "2_2") (pintype "input"))
      (node (ref "C15") (pin "1") (pinfunction "1_1") (pintype "input"))
      (node (ref "C16") (pin "2") (pinfunction "2_2") (pintype "input"))
      (node (ref "C17") (pin "1") (pinfunction "1_1") (pintype "input"))
      (node (ref "C2") (pin "1") (pinfunction "1_1") (pintype "input"))
      (node (ref "C4") (pin "1") (pinfunction "1_1") (pintype "input"))
      (node (ref "C5") (pin "1") (pinfunction "1_1") (pintype "input"))
      (node (ref "C6") (pin "1") (pinfunction "1_1") (pintype "input"))
      (node (ref "D4") (pin "1") (pinfunction "K_1") (pintype "input"))
      (node (ref "D5") (pin "1") (pinfunction "K_1") (pintype "input"))
      (node (ref "D6") (pin "1") (pinfunction "K_1") (pintype "input"))
      (node (ref "H1") (pin "1") (pinfunction "1_1") (pintype "bidirectional"))
      (node (ref "H2") (pin "1") (pinfunction "1_1") (pintype "bidirectional"))
      (node (ref "H3") (pin "1") (pinfunction "1_1") (pintype "bidirectional"))
      (node (ref "H4") (pin "1") (pinfunction "1_1") (pintype "bidirectional"))
      (node (ref "J10") (pin "1") (pinfunction "1_1") (pintype "input"))
      (node (ref "J10") (pin "17") (pinfunction "17_17") (pintype "input"))
      (node (ref "J10") (pin "19") (pinfunction "19_19") (pintype "input"))
      (node (ref "J10") (pin "3") (pinfunction "3_3") (pintype "input"))
      (node (ref "J11") (pin "21") (pinfunction "21_21") (pintype "input"))
      (node (ref "J11") (pin "22") (pinfunction "22_22") (pintype "input"))
      (node (ref "J12") (pin "2") (pinfunction "2_2") (pintype "input"))
      (node (ref "J13") (pin "2") (pinfunction "2_2") (pintype "input"))
      (node (ref "J14") (pin "5") (pinfunction "5_5") (pintype "input"))
      (node (ref "J14") (pin "6") (pinfunction "6_6") (pintype "input"))
      (node (ref "J16") (pin "5") (pinfunction "5_5") (pintype "input"))
      (node (ref "J17") (pin "2") (pinfunction "2_2") (pintype "input"))
      (node (ref "J3") (pin "3") (pinfunction "3_3") (pintype "input"))
      (node (ref "J4") (pin "3") (pinfunction "3_3") (pintype "input"))
      (node (ref "J5") (pin "6") (pinfunction "6_6") (pintype "input"))
      (node (ref "J9") (pin "4") (pinfunction "4_4") (pintype "input"))
      (node (ref "L2") (pin "2") (pinfunction "2_2") (pintype "input"))
      (node (ref "Q1") (pin "3") (pinfunction "E_3") (pintype "unspecified"))
      (node (ref "R6") (pin "1") (pinfunction "1_1") (pintype "input"))
      (node (ref "R7") (pin "1") (pinfunction "1_1") (pintype "input"))
      (node (ref "S2") (pin "5") (pinfunction "5_5") (pintype "input"))
      (node (ref "S2") (pin "6") (pinfunction "6_6") (pintype "input"))
      (node (ref "S2") (pin "7") (pinfunction "7_7") (pintype "input"))
      (node (ref "S2") (pin "8") (pinfunction "8_8") (pintype "input"))
      (node (ref "U1") (pin "2") (pinfunction "GND_2") (pintype "input"))
      (node (ref "U2") (pin "1") (pinfunction "SD_1") (pintype "input"))
      (node (ref "U2") (pin "3") (pinfunction "GND_3") (pintype "input"))
      (node (ref "U2") (pin "6") (pinfunction "LV_6") (pintype "input"))
      (node (ref "U2") (pin "7") (pinfunction "OSC_7") (pintype "input"))
      (node (ref "U4") (pin "2") (pinfunction "GND_2") (pintype "input"))
      (node (ref "U5") (pin "2") (pinfunction "2_2") (pintype "input"))
    )
    (net (code "41") (name "Net-(D1-C)") (class "Default")
      (node (ref "C1") (pin "2") (pinfunction "2_2") (pintype "input"))
      (node (ref "D1") (pin "1") (pinfunction "C_1") (pintype "input"))
      (node (ref "U1") (pin "1") (pinfunction "IN_1") (pintype "input"))
      (node (ref "U1") (pin "3") (pinfunction "EN_3") (pintype "input"))
    )
    (net (code "42") (name "Net-(D2-C)") (class "Default")
      (node (ref "C8") (pin "2") (pinfunction "2_2") (pintype "input"))
      (node (ref "C9") (pin "1") (pinfunction "1_1") (pintype "input"))
      (node (ref "D2") (pin "1") (pinfunction "C_1") (pintype "input"))
      (node (ref "LM1") (pin "1") (pinfunction "VIN_1") (pintype "input"))
    )
    (net (code "43") (name "Net-(D3-C)") (class "Default")
      (node (ref "D3") (pin "1") (pinfunction "C_1") (pintype "input"))
      (node (ref "U4") (pin "1") (pinfunction "IN_1") (pintype "input"))
      (node (ref "U4") (pin "3") (pinfunction "EN_3") (pintype "input"))
      (node (ref "U5") (pin "1") (pinfunction "1_1") (pintype "input"))
    )
    (net (code "44") (name "Net-(D4-A)") (class "Default")
      (node (ref "D4") (pin "2") (pinfunction "A_2") (pintype "input"))
      (node (ref "R12") (pin "1") (pinfunction "1_1") (pintype "input"))
    )
    (net (code "45") (name "Net-(D5-A)") (class "Default")
      (node (ref "D5") (pin "2") (pinfunction "A_2") (pintype "input"))
      (node (ref "R13") (pin "1") (pinfunction "1_1") (pintype "input"))
    )
    (net (code "46") (name "Net-(D6-A)") (class "Default")
      (node (ref "D6") (pin "2") (pinfunction "A_2") (pintype "input"))
      (node (ref "R14") (pin "1") (pinfunction "1_1") (pintype "input"))
    )
    (net (code "47") (name "Net-(D7-A)") (class "Default")
      (node (ref "D7") (pin "2") (pinfunction "A_2") (pintype "input"))
      (node (ref "R15") (pin "1") (pinfunction "1_1") (pintype "input"))
    )
    (net (code "48") (name "Net-(D8-A)") (class "Default")
      (node (ref "D8") (pin "2") (pinfunction "A_2") (pintype "input"))
      (node (ref "R16") (pin "1") (pinfunction "1_1") (pintype "input"))
    )
    (net (code "49") (name "Net-(D9-A)") (class "Default")
      (node (ref "D9") (pin "2") (pinfunction "A_2") (pintype "input"))
      (node (ref "LS1") (pin "2") (pinfunction "2_2") (pintype "input"))
      (node (ref "Q1") (pin "2") (pinfunction "C_2") (pintype "unspecified"))
    )
    (net (code "50") (name "Net-(J4-Pad1)") (class "Default")
      (node (ref "J4") (pin "1") (pinfunction "1_1") (pintype "input"))
      (node (ref "L1") (pin "2") (pinfunction "2_2") (pintype "input"))
    )
    (net (code "51") (name "Net-(J8-Pad5)") (class "Default")
      (node (ref "J8") (pin "5") (pinfunction "5_5") (pintype "input"))
      (node (ref "J8") (pin "6") (pinfunction "6_6") (pintype "input"))
      (node (ref "S3") (pin "2") (pinfunction "2_2") (pintype "input"))
    )
    (net (code "52") (name "Net-(Q1-B)") (class "Default")
      (node (ref "Q1") (pin "1") (pinfunction "B_1") (pintype "unspecified"))
      (node (ref "R31") (pin "2") (pinfunction "2_2") (pintype "input"))
    )
    (net (code "53") (name "Net-(U2-CAP+)") (class "Default")
      (node (ref "C3") (pin "2") (pinfunction "2_2") (pintype "input"))
      (node (ref "U2") (pin "2") (pinfunction "CAP+_2") (pintype "input"))
    )
    (net (code "54") (name "Net-(U2-CAP-)") (class "Default")
      (node (ref "C3") (pin "1") (pinfunction "1_1") (pintype "input"))
      (node (ref "U2") (pin "4") (pinfunction "CAP-_4") (pintype "input"))
    )
    (net (code "55") (name "Net-(U3-CAT1)") (class "Default")
      (node (ref "R3") (pin "2") (pinfunction "2_2") (pintype "input"))
      (node (ref "U3") (pin "2") (pinfunction "CAT1_2") (pintype "input"))
    )
    (net (code "56") (name "Net-(U3-CAT2)") (class "Default")
      (node (ref "R4") (pin "2") (pinfunction "2_2") (pintype "input"))
      (node (ref "U3") (pin "3") (pinfunction "CAT2_3") (pintype "input"))
    )
    (net (code "57") (name "Net-(U4-NR{slash}FB)") (class "Default")
      (node (ref "R5") (pin "1") (pinfunction "1_1") (pintype "input"))
      (node (ref "R7") (pin "2") (pinfunction "2_2") (pintype "input"))
      (node (ref "U4") (pin "4") (pinfunction "NR/FB_4") (pintype "input"))
    )
    (net (code "58") (name "Net-(U6-CAT1)") (class "Default")
      (node (ref "R10") (pin "2") (pinfunction "2_2") (pintype "input"))
      (node (ref "U6") (pin "2") (pinfunction "CAT1_2") (pintype "input"))
    )
    (net (code "59") (name "Net-(U6-CAT2)") (class "Default")
      (node (ref "R11") (pin "2") (pinfunction "2_2") (pintype "input"))
      (node (ref "U6") (pin "3") (pinfunction "CAT2_3") (pintype "input"))
    )
    (net (code "60") (name "Net-(U7-CAT1)") (class "Default")
      (node (ref "R21") (pin "2") (pinfunction "2_2") (pintype "input"))
      (node (ref "U7") (pin "2") (pinfunction "CAT1_2") (pintype "input"))
    )
    (net (code "61") (name "Net-(U7-CAT2)") (class "Default")
      (node (ref "R24") (pin "2") (pinfunction "2_2") (pintype "input"))
      (node (ref "U7") (pin "3") (pinfunction "CAT2_3") (pintype "input"))
    )
    (net (code "62") (name "Net-(U7-VO2)") (class "Default")
      (node (ref "R18") (pin "1") (pinfunction "1_1") (pintype "input"))
      (node (ref "U7") (pin "6") (pinfunction "VO2_6") (pintype "input"))
    )
    (net (code "63") (name "V5") (class "Default")
      (node (ref "C10") (pin "2") (pinfunction "2_2") (pintype "input"))
      (node (ref "C13") (pin "1") (pinfunction "1_1") (pintype "input"))
      (node (ref "C14") (pin "2") (pinfunction "2_2") (pintype "input"))
      (node (ref "L1") (pin "1") (pinfunction "1_1") (pintype "input"))
      (node (ref "LM1") (pin "3") (pinfunction "VOUT_3") (pintype "input"))
      (node (ref "R1") (pin "2") (pinfunction "2_2") (pintype "input"))
      (node (ref "R16") (pin "2") (pinfunction "2_2") (pintype "input"))
      (node (ref "R18") (pin "2") (pinfunction "2_2") (pintype "input"))
      (node (ref "R19") (pin "2") (pinfunction "2_2") (pintype "input"))
      (node (ref "R2") (pin "2") (pinfunction "2_2") (pintype "input"))
      (node (ref "R8") (pin "2") (pinfunction "2_2") (pintype "input"))
      (node (ref "R9") (pin "2") (pinfunction "2_2") (pintype "input"))
      (node (ref "U3") (pin "8") (pinfunction "VCC_8") (pintype "input"))
      (node (ref "U6") (pin "8") (pinfunction "VCC_8") (pintype "input"))
      (node (ref "U7") (pin "8") (pinfunction "VCC_8") (pintype "input"))
    )
    (net (code "64") (name "V6") (class "Default")
      (node (ref "C11") (pin "1") (pinfunction "1_1") (pintype "input"))
      (node (ref "J15") (pin "2") (pinfunction "2_2") (pintype "input"))
      (node (ref "R15") (pin "2") (pinfunction "2_2") (pintype "input"))
      (node (ref "R5") (pin "2") (pinfunction "2_2") (pintype "input"))
      (node (ref "R6") (pin "2") (pinfunction "2_2") (pintype "input"))
      (node (ref "U4") (pin "5") (pinfunction "OUT_5") (pintype "input"))
    )
    (net (code "65") (name "VBAT") (class "Default")
      (node (ref "C7") (pin "1") (pinfunction "1_1") (pintype "input"))
      (node (ref "D2") (pin "2") (pinfunction "A_2") (pintype "input"))
      (node (ref "D3") (pin "2") (pinfunction "A_2") (pintype "input"))
      (node (ref "S1") (pin "1") (pinfunction "1_1") (pintype "input"))
    )
    (net (code "66") (name "VBAT+") (class "Default")
      (node (ref "J2") (pin "1") (pinfunction "1_1") (pintype "input"))
      (node (ref "S1") (pin "2") (pinfunction "2_2") (pintype "input"))
    )
    (net (code "67") (name "VCC-5") (class "Default")
      (node (ref "C5") (pin "2") (pinfunction "2_2") (pintype "input"))
      (node (ref "C6") (pin "2") (pinfunction "2_2") (pintype "input"))
      (node (ref "J7") (pin "10") (pinfunction "10_10") (pintype "input"))
      (node (ref "J7") (pin "11") (pinfunction "11_11") (pintype "input"))
      (node (ref "J7") (pin "12") (pinfunction "12_12") (pintype "input"))
      (node (ref "J7") (pin "9") (pinfunction "9_9") (pintype "input"))
      (node (ref "R14") (pin "2") (pinfunction "2_2") (pintype "input"))
      (node (ref "U2") (pin "5") (pinfunction "OUT_5") (pintype "input"))
    )
    (net (code "68") (name "VCC3.3") (class "Default")
      (node (ref "C2") (pin "2") (pinfunction "2_2") (pintype "input"))
      (node (ref "J12") (pin "1") (pinfunction "1_1") (pintype "input"))
      (node (ref "J16") (pin "4") (pinfunction "4_4") (pintype "input"))
      (node (ref "J3") (pin "1") (pinfunction "1_1") (pintype "input"))
      (node (ref "J5") (pin "5") (pinfunction "5_5") (pintype "input"))
      (node (ref "J9") (pin "1") (pinfunction "1_1") (pintype "input"))
      (node (ref "R12") (pin "2") (pinfunction "2_2") (pintype "input"))
      (node (ref "R17") (pin "2") (pinfunction "2_2") (pintype "input"))
      (node (ref "R20") (pin "2") (pinfunction "2_2") (pintype "input"))
      (node (ref "R22") (pin "2") (pinfunction "2_2") (pintype "input"))
      (node (ref "R23") (pin "2") (pinfunction "2_2") (pintype "input"))
      (node (ref "R25") (pin "2") (pinfunction "2_2") (pintype "input"))
      (node (ref "R30") (pin "2") (pinfunction "2_2") (pintype "input"))
      (node (ref "U1") (pin "5") (pinfunction "OUT_5") (pintype "input"))
    )
    (net (code "69") (name "VCC5") (class "Default")
      (node (ref "C15") (pin "2") (pinfunction "2_2") (pintype "input"))
      (node (ref "C16") (pin "1") (pinfunction "1_1") (pintype "input"))
      (node (ref "C17") (pin "2") (pinfunction "2_2") (pintype "input"))
      (node (ref "C4") (pin "2") (pinfunction "2_2") (pintype "input"))
      (node (ref "D1") (pin "2") (pinfunction "A_2") (pintype "input"))
      (node (ref "D9") (pin "1") (pinfunction "C_1") (pintype "input"))
      (node (ref "J14") (pin "7") (pinfunction "7_7") (pintype "input"))
      (node (ref "J14") (pin "8") (pinfunction "8_8") (pintype "input"))
      (node (ref "J4") (pin "4") (pinfunction "4_4") (pintype "input"))
      (node (ref "J7") (pin "1") (pinfunction "1_1") (pintype "input"))
      (node (ref "J7") (pin "2") (pinfunction "2_2") (pintype "input"))
      (node (ref "J7") (pin "3") (pinfunction "3_3") (pintype "input"))
      (node (ref "J7") (pin "4") (pinfunction "4_4") (pintype "input"))
      (node (ref "LS1") (pin "1") (pinfunction "+_1") (pintype "input"))
      (node (ref "R13") (pin "2") (pinfunction "2_2") (pintype "input"))
      (node (ref "R26") (pin "2") (pinfunction "2_2") (pintype "input"))
      (node (ref "R27") (pin "2") (pinfunction "2_2") (pintype "input"))
      (node (ref "R28") (pin "2") (pinfunction "2_2") (pintype "input"))
      (node (ref "R29") (pin "2") (pinfunction "2_2") (pintype "input"))
      (node (ref "U2") (pin "8") (pinfunction "V+_8") (pintype "input"))
      (node (ref "U3") (pin "1") (pinfunction "AN1_1") (pintype "input"))
      (node (ref "U3") (pin "4") (pinfunction "AN2_4") (pintype "input"))
      (node (ref "U6") (pin "1") (pinfunction "AN1_1") (pintype "input"))
      (node (ref "U6") (pin "4") (pinfunction "AN2_4") (pintype "input"))
      (node (ref "U7") (pin "1") (pinfunction "AN1_1") (pintype "input"))
      (node (ref "U7") (pin "4") (pinfunction "AN2_4") (pintype "input"))
    )
    (net (code "70") (name "unconnected-(J10-Pad7)") (class "Default")
      (node (ref "J10") (pin "7") (pinfunction "7_7") (pintype "input+no_connect"))
    )
    (net (code "71") (name "unconnected-(J10-Pad8)") (class "Default")
      (node (ref "J10") (pin "8") (pinfunction "8_8") (pintype "input+no_connect"))
    )
    (net (code "72") (name "unconnected-(J10-Pad9)") (class "Default")
      (node (ref "J10") (pin "9") (pinfunction "9_9") (pintype "input+no_connect"))
    )
    (net (code "73") (name "unconnected-(J10-Pad10)") (class "Default")
      (node (ref "J10") (pin "10") (pinfunction "10_10") (pintype "input+no_connect"))
    )
    (net (code "74") (name "unconnected-(J10-Pad16)") (class "Default")
      (node (ref "J10") (pin "16") (pinfunction "16_16") (pintype "input+no_connect"))
    )
    (net (code "75") (name "unconnected-(J10-Pad18)") (class "Default")
      (node (ref "J10") (pin "18") (pinfunction "18_18") (pintype "input+no_connect"))
    )
    (net (code "76") (name "unconnected-(J11-Pad6)") (class "Default")
      (node (ref "J11") (pin "6") (pinfunction "6_6") (pintype "input+no_connect"))
    )
    (net (code "77") (name "unconnected-(J11-Pad7)") (class "Default")
      (node (ref "J11") (pin "7") (pinfunction "7_7") (pintype "input+no_connect"))
    )
    (net (code "78") (name "unconnected-(J11-Pad8)") (class "Default")
      (node (ref "J11") (pin "8") (pinfunction "8_8") (pintype "input+no_connect"))
    )
    (net (code "79") (name "unconnected-(J11-Pad10)") (class "Default")
      (node (ref "J11") (pin "10") (pinfunction "10_10") (pintype "input+no_connect"))
    )
    (net (code "80") (name "unconnected-(J11-Pad13)") (class "Default")
      (node (ref "J11") (pin "13") (pinfunction "13_13") (pintype "input+no_connect"))
    )
    (net (code "81") (name "unconnected-(J11-Pad14)") (class "Default")
      (node (ref "J11") (pin "14") (pinfunction "14_14") (pintype "input+no_connect"))
    )
    (net (code "82") (name "unconnected-(J11-Pad15)") (class "Default")
      (node (ref "J11") (pin "15") (pinfunction "15_15") (pintype "input+no_connect"))
    )
    (net (code "83") (name "unconnected-(J11-Pad17)") (class "Default")
      (node (ref "J11") (pin "17") (pinfunction "17_17") (pintype "input+no_connect"))
    )
    (net (code "84") (name "unconnected-(J11-Pad18)") (class "Default")
      (node (ref "J11") (pin "18") (pinfunction "18_18") (pintype "input+no_connect"))
    )
    (net (code "85") (name "unconnected-(J11-Pad19)") (class "Default")
      (node (ref "J11") (pin "19") (pinfunction "19_19") (pintype "input+no_connect"))
    )
    (net (code "86") (name "unconnected-(J11-Pad20)") (class "Default")
      (node (ref "J11") (pin "20") (pinfunction "20_20") (pintype "input+no_connect"))
    )
    (net (code "87") (name "unconnected-(J12-Pad11)") (class "Default")
      (node (ref "J12") (pin "11") (pinfunction "11_11") (pintype "input+no_connect"))
    )
    (net (code "88") (name "unconnected-(J12-Pad12)") (class "Default")
      (node (ref "J12") (pin "12") (pinfunction "12_12") (pintype "input+no_connect"))
    )
    (net (code "89") (name "unconnected-(J12-Pad13)") (class "Default")
      (node (ref "J12") (pin "13") (pinfunction "13_13") (pintype "input+no_connect"))
    )
    (net (code "90") (name "unconnected-(J12-Pad14)") (class "Default")
      (node (ref "J12") (pin "14") (pinfunction "14_14") (pintype "input+no_connect"))
    )
    (net (code "91") (name "unconnected-(J12-Pad15)") (class "Default")
      (node (ref "J12") (pin "15") (pinfunction "15_15") (pintype "input+no_connect"))
    )
    (net (code "92") (name "unconnected-(J12-Pad16)") (class "Default")
      (node (ref "J12") (pin "16") (pinfunction "16_16") (pintype "input+no_connect"))
    )
    (net (code "93") (name "unconnected-(R24-Pad1)") (class "Default")
      (node (ref "R24") (pin "1") (pinfunction "1_1") (pintype "input+no_connect"))
    )
    (net (code "94") (name "unconnected-(U1-NR{slash}FB-Pad4)") (class "Default")
      (node (ref "U1") (pin "4") (pinfunction "NR/FB_4") (pintype "input+no_connect"))
    )
  )
)
